# SwitchBoard.net
KiCad netlist of a schematic drawn in EAGLE
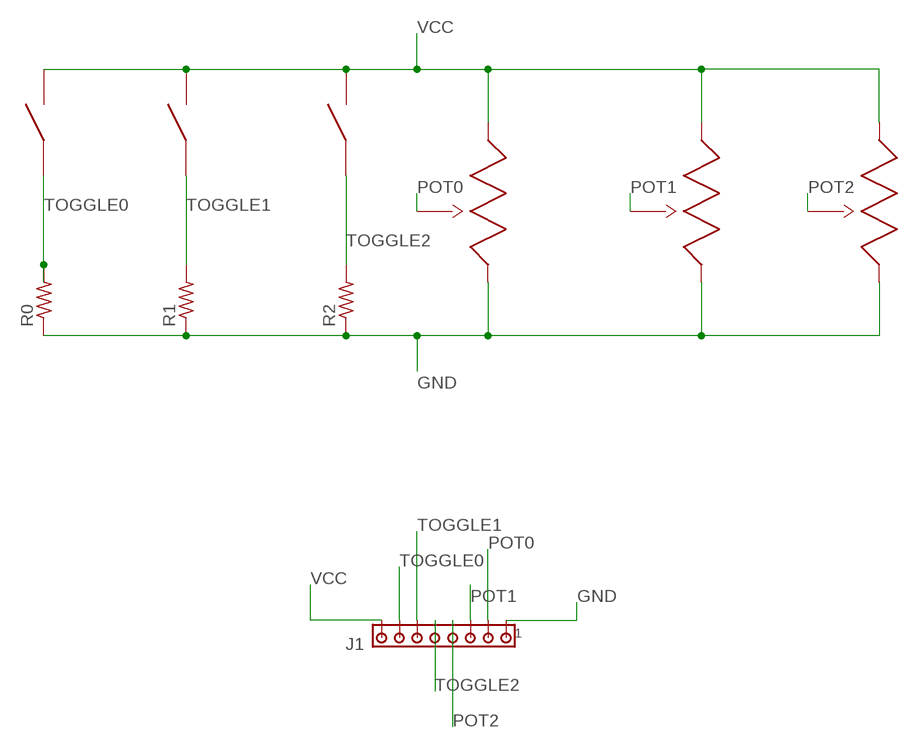
[diagram p0: schematic, sheet 1]

(export (version "E")
  (design (tool "Eeschema 10.0.6"))
  (components
    (comp (ref "J1")
      (value "MTA08-100")
      (footprint "eagle-import:10X08MTA")
      (libsource (lib "eagle-import") (part "MTA08-100"))
    )
    (comp (ref "POT0")
      (value "PRS11S-11")
      (footprint "eagle-import:POT-SMD")
      (libsource (lib "eagle-import") (part "PRS11S-11"))
    )
    (comp (ref "POT1")
      (value "PRS11S-11")
      (footprint "eagle-import:POT-SMD")
      (libsource (lib "eagle-import") (part "PRS11S-11"))
    )
    (comp (ref "POT2")
      (value "PRS11S-11")
      (footprint "eagle-import:POT-SMD")
      (libsource (lib "eagle-import") (part "PRS11S-11"))
    )
    (comp (ref "R0")
      (value "R-US_0204/5")
      (footprint "eagle-import:0204_5")
      (libsource (lib "eagle-import") (part "R-US_0204/5"))
    )
    (comp (ref "R1")
      (value "R-US_0204/5")
      (footprint "eagle-import:0204_5")
      (libsource (lib "eagle-import") (part "R-US_0204/5"))
    )
    (comp (ref "R2")
      (value "R-US_0204/5")
      (footprint "eagle-import:0204_5")
      (libsource (lib "eagle-import") (part "R-US_0204/5"))
    )
    (comp (ref "TOGGLE0")
      (value "COM-09276")
      (footprint "eagle-import:SPST-TOGGLE-SWITCH")
      (libsource (lib "eagle-import") (part "COM-09276"))
    )
    (comp (ref "TOGGLE1")
      (value "COM-09276")
      (footprint "eagle-import:SPST-TOGGLE-SWITCH")
      (libsource (lib "eagle-import") (part "COM-09276"))
    )
    (comp (ref "TOGGLE2")
      (value "COM-09276")
      (footprint "eagle-import:SPST-TOGGLE-SWITCH")
      (libsource (lib "eagle-import") (part "COM-09276"))
    )
  )
  (nets
    (net (code "1") (name "/GND") (class "Default")
      (node (ref "J1") (pin "1") (pinfunction "1_1") (pintype "passive"))
      (node (ref "POT0") (pin "1") (pinfunction "1_1") (pintype "bidirectional"))
      (node (ref "POT1") (pin "1") (pinfunction "1_1") (pintype "bidirectional"))
      (node (ref "POT2") (pin "1") (pinfunction "1_1") (pintype "bidirectional"))
      (node (ref "R0") (pin "1") (pinfunction "1_1") (pintype "passive"))
      (node (ref "R1") (pin "1") (pinfunction "1_1") (pintype "passive"))
      (node (ref "R2") (pin "1") (pinfunction "1_1") (pintype "passive"))
    )
    (net (code "2") (name "/POT0") (class "Default")
      (node (ref "J1") (pin "2") (pinfunction "2_2") (pintype "passive"))
      (node (ref "POT0") (pin "2") (pinfunction "2_2") (pintype "bidirectional"))
    )
    (net (code "3") (name "/POT1") (class "Default")
      (node (ref "J1") (pin "3") (pinfunction "3_3") (pintype "passive"))
      (node (ref "POT1") (pin "2") (pinfunction "2_2") (pintype "bidirectional"))
    )
    (net (code "4") (name "/POT2") (class "Default")
      (node (ref "J1") (pin "4") (pinfunction "4_4") (pintype "passive"))
      (node (ref "POT2") (pin "2") (pinfunction "2_2") (pintype "bidirectional"))
    )
    (net (code "5") (name "/TOGGLE0") (class "Default")
      (node (ref "J1") (pin "7") (pinfunction "7_7") (pintype "passive"))
      (node (ref "R0") (pin "2") (pinfunction "2_2") (pintype "passive"))
      (node (ref "TOGGLE0") (pin "1") (pinfunction "1_1") (pintype "bidirectional"))
    )
    (net (code "6") (name "/TOGGLE1") (class "Default")
      (node (ref "J1") (pin "6") (pinfunction "6_6") (pintype "passive"))
      (node (ref "R1") (pin "2") (pinfunction "2_2") (pintype "passive"))
      (node (ref "TOGGLE1") (pin "1") (pinfunction "1_1") (pintype "bidirectional"))
    )
    (net (code "7") (name "/TOGGLE2") (class "Default")
      (node (ref "J1") (pin "5") (pinfunction "5_5") (pintype "passive"))
      (node (ref "R2") (pin "2") (pinfunction "2_2") (pintype "passive"))
      (node (ref "TOGGLE2") (pin "1") (pinfunction "1_1") (pintype "bidirectional"))
    )
    (net (code "8") (name "/VCC") (class "Default")
      (node (ref "J1") (pin "8") (pinfunction "8_8") (pintype "passive"))
      (node (ref "POT0") (pin "3") (pinfunction "3_3") (pintype "bidirectional"))
      (node (ref "POT1") (pin "3") (pinfunction "3_3") (pintype "bidirectional"))
      (node (ref "POT2") (pin "3") (pinfunction "3_3") (pintype "bidirectional"))
      (node (ref "TOGGLE0") (pin "2") (pinfunction "2_2") (pintype "bidirectional"))
      (node (ref "TOGGLE1") (pin "2") (pinfunction "2_2") (pintype "bidirectional"))
      (node (ref "TOGGLE2") (pin "2") (pinfunction "2_2") (pintype "bidirectional"))
    )
  )
)
